# pixelAdapter_f070f6.net
KiCad netlist of a schematic drawn in EAGLE
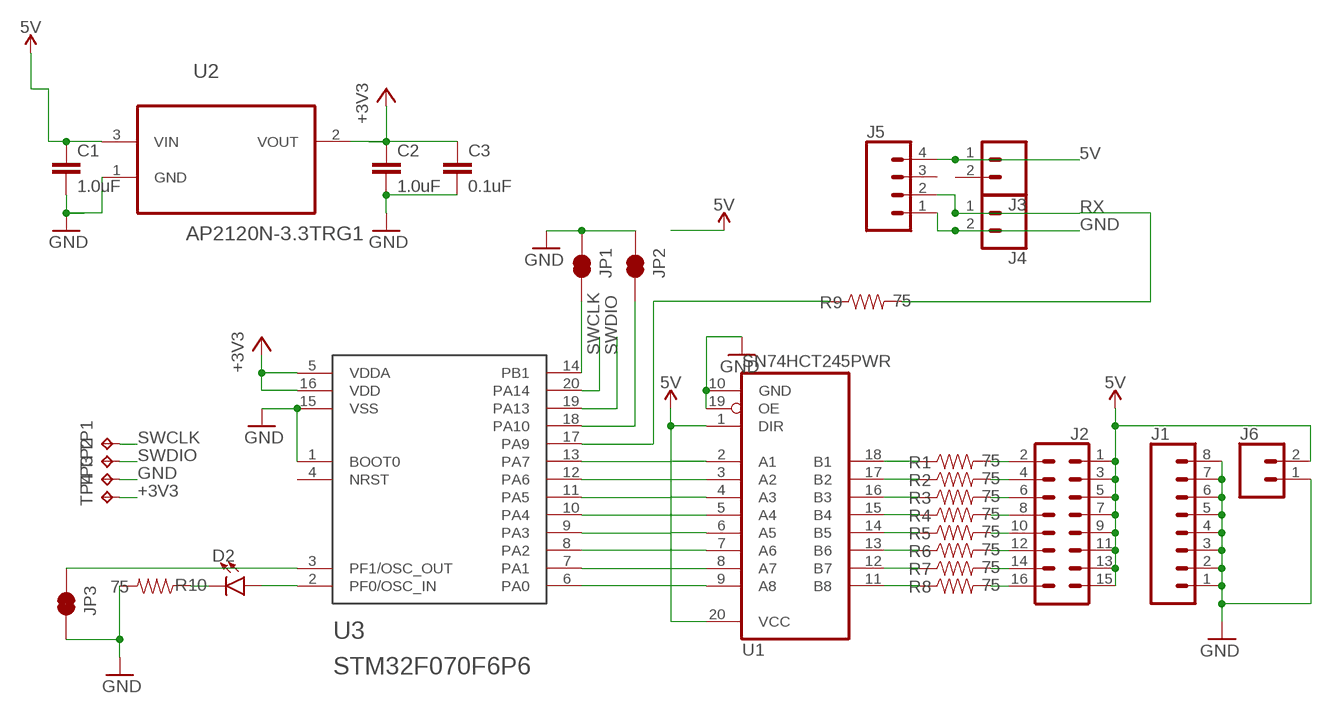
[diagram p0: schematic, sheet 1]

(export (version "E")
  (design (tool "Eeschema 10.0.6"))
  (components
    (comp (ref "C1")
      (value "1.0uF")
      (footprint "eagle-import:0603")
      (libsource (lib "eagle-import") (part "1.0UF-0603-16V-10%"))
    )
    (comp (ref "C2")
      (value "1.0uF")
      (footprint "eagle-import:0603")
      (libsource (lib "eagle-import") (part "1.0UF-0603-16V-10%"))
    )
    (comp (ref "C3")
      (value "0.1uF")
      (footprint "eagle-import:0603")
      (libsource (lib "eagle-import") (part "0.1UF-0603-25V-(+80/-20%)"))
    )
    (comp (ref "D2")
      (value "LED0603")
      (footprint "eagle-import:LED-0603")
      (libsource (lib "eagle-import") (part "LED0603"))
    )
    (comp (ref "J1")
      (value "CONN_08\"")
      (footprint "eagle-import:1X08")
      (libsource (lib "eagle-import") (part "CONN_08{dblquote}"))
    )
    (comp (ref "J2")
      (value "CONN_08X2")
      (footprint "eagle-import:2X8")
      (libsource (lib "eagle-import") (part "CONN_08X2"))
    )
    (comp (ref "J3")
      (value "CONN_025MM")
      (footprint "eagle-import:SCREWTERMINAL-5MM-2")
      (libsource (lib "eagle-import") (part "bens_CONN_025MM"))
    )
    (comp (ref "J4")
      (value "CONN_025MM")
      (footprint "eagle-import:SCREWTERMINAL-5MM-2")
      (libsource (lib "eagle-import") (part "bens_CONN_025MM"))
    )
    (comp (ref "J5")
      (value "CONN_04LOCK")
      (footprint "eagle-import:1X04_LOCK")
      (libsource (lib "eagle-import") (part "CONN_04LOCK"))
    )
    (comp (ref "J6")
      (value "CONN_02")
      (footprint "eagle-import:1X02")
      (libsource (lib "eagle-import") (part "CONN_02"))
    )
    (comp (ref "JP1")
      (value "JUMPER-SMT_2_NC_TRACE_SILK")
      (footprint "eagle-import:SMT-JUMPER_2_NC_TRACE_SILK")
      (libsource (lib "eagle-import") (part "JUMPER-SMT_2_NC_TRACE_SILK"))
    )
    (comp (ref "JP2")
      (value "JUMPER-SMT_2_NC_TRACE_SILK")
      (footprint "eagle-import:SMT-JUMPER_2_NC_TRACE_SILK")
      (libsource (lib "eagle-import") (part "JUMPER-SMT_2_NC_TRACE_SILK"))
    )
    (comp (ref "JP3")
      (value "JUMPER-SMT_2_NC_TRACE_SILK")
      (footprint "eagle-import:SMT-JUMPER_2_NC_TRACE_SILK")
      (libsource (lib "eagle-import") (part "JUMPER-SMT_2_NC_TRACE_SILK"))
    )
    (comp (ref "R1")
      (value "75")
      (footprint "eagle-import:0603")
      (libsource (lib "eagle-import") (part "100OHM-0603-1/4W-5%"))
    )
    (comp (ref "R2")
      (value "75")
      (footprint "eagle-import:0603")
      (libsource (lib "eagle-import") (part "100OHM-0603-1/4W-5%"))
    )
    (comp (ref "R3")
      (value "75")
      (footprint "eagle-import:0603")
      (libsource (lib "eagle-import") (part "100OHM-0603-1/4W-5%"))
    )
    (comp (ref "R4")
      (value "75")
      (footprint "eagle-import:0603")
      (libsource (lib "eagle-import") (part "100OHM-0603-1/4W-5%"))
    )
    (comp (ref "R5")
      (value "75")
      (footprint "eagle-import:0603")
      (libsource (lib "eagle-import") (part "100OHM-0603-1/4W-5%"))
    )
    (comp (ref "R6")
      (value "75")
      (footprint "eagle-import:0603")
      (libsource (lib "eagle-import") (part "100OHM-0603-1/4W-5%"))
    )
    (comp (ref "R7")
      (value "75")
      (footprint "eagle-import:0603")
      (libsource (lib "eagle-import") (part "100OHM-0603-1/4W-5%"))
    )
    (comp (ref "R8")
      (value "75")
      (footprint "eagle-import:0603")
      (libsource (lib "eagle-import") (part "100OHM-0603-1/4W-5%"))
    )
    (comp (ref "R9")
      (value "75")
      (footprint "eagle-import:0603")
      (libsource (lib "eagle-import") (part "100OHM-0603-1/4W-5%"))
    )
    (comp (ref "R10")
      (value "75")
      (footprint "eagle-import:0603")
      (libsource (lib "eagle-import") (part "100OHM-0603-1/4W-5%"))
    )
    (comp (ref "TP1")
      (value "TPTP20SQ")
      (footprint "eagle-import:TP20SQ")
      (libsource (lib "eagle-import") (part "TPTP20SQ"))
    )
    (comp (ref "TP2")
      (value "TPTP20SQ")
      (footprint "eagle-import:TP20SQ")
      (libsource (lib "eagle-import") (part "TPTP20SQ"))
    )
    (comp (ref "TP3")
      (value "TPTP20SQ")
      (footprint "eagle-import:TP20SQ")
      (libsource (lib "eagle-import") (part "TPTP20SQ"))
    )
    (comp (ref "TP4")
      (value "TPTP20SQ")
      (footprint "eagle-import:TP20SQ")
      (libsource (lib "eagle-import") (part "TPTP20SQ"))
    )
    (comp (ref "U1")
      (value "SN74HCT245PWR")
      (footprint "eagle-import:TSSOP20")
      (libsource (lib "eagle-import") (part "74245PW"))
    )
    (comp (ref "U2")
      (value "AP2120N-3.3TRG1")
      (footprint "eagle-import:SOT95P237X112-3N")
      (fields (field (name "MPN") "MCP1700T-3302E/TT"))
      (libsource (lib "eagle-import") (part "MCP1700T-3302E/TT"))
    )
    (comp (ref "U3")
      (value "STM32F070F6P6")
      (footprint "eagle-import:TSSOP-20")
      (libsource (lib "eagle-import") (part "STM32F030XTSSOP20"))
    )
  )
  (nets
    (net (code "1") (name "+3V3") (class "Default")
      (node (ref "C2") (pin "1") (pinfunction "1_1") (pintype "passive"))
      (node (ref "C3") (pin "1") (pinfunction "1_1") (pintype "passive"))
      (node (ref "TP4") (pin "TP") (pinfunction "TP_TP") (pintype "input"))
      (node (ref "U2") (pin "2") (pinfunction "VOUT_2") (pintype "output"))
      (node (ref "U3") (pin "16") (pinfunction "VDD_16") (pintype "bidirectional"))
      (node (ref "U3") (pin "5") (pinfunction "VDDA_5") (pintype "bidirectional"))
    )
    (net (code "2") (name "/RX") (class "Default")
      (node (ref "J4") (pin "1") (pinfunction "1_1") (pintype "passive"))
      (node (ref "J5") (pin "2") (pinfunction "2_2") (pintype "passive"))
      (node (ref "R9") (pin "2") (pinfunction "2_2") (pintype "passive"))
    )
    (net (code "3") (name "/SWCLK") (class "Default")
      (node (ref "TP1") (pin "TP") (pinfunction "TP_TP") (pintype "input"))
      (node (ref "U3") (pin "20") (pinfunction "PA14_20") (pintype "bidirectional"))
    )
    (net (code "4") (name "/SWDIO") (class "Default")
      (node (ref "TP2") (pin "TP") (pinfunction "TP_TP") (pintype "input"))
      (node (ref "U3") (pin "19") (pinfunction "PA13_19") (pintype "bidirectional"))
    )
    (net (code "5") (name "5V") (class "Default")
      (node (ref "C1") (pin "1") (pinfunction "1_1") (pintype "passive"))
      (node (ref "J2") (pin "1") (pinfunction "1_1") (pintype "passive"))
      (node (ref "J2") (pin "11") (pinfunction "11_11") (pintype "passive"))
      (node (ref "J2") (pin "13") (pinfunction "13_13") (pintype "passive"))
      (node (ref "J2") (pin "15") (pinfunction "15_15") (pintype "passive"))
      (node (ref "J2") (pin "3") (pinfunction "3_3") (pintype "passive"))
      (node (ref "J2") (pin "5") (pinfunction "5_5") (pintype "passive"))
      (node (ref "J2") (pin "7") (pinfunction "7_7") (pintype "passive"))
      (node (ref "J2") (pin "9") (pinfunction "9_9") (pintype "passive"))
      (node (ref "J3") (pin "1") (pinfunction "1_1") (pintype "passive"))
      (node (ref "J5") (pin "4") (pinfunction "4_4") (pintype "passive"))
      (node (ref "J6") (pin "2") (pinfunction "2_2") (pintype "passive"))
      (node (ref "U1") (pin "1") (pinfunction "DIR_1") (pintype "input"))
      (node (ref "U1") (pin "20") (pinfunction "VCC_20") (pintype "bidirectional"))
      (node (ref "U2") (pin "3") (pinfunction "VIN_3") (pintype "input"))
    )
    (net (code "6") (name "GND") (class "Default")
      (node (ref "C1") (pin "2") (pinfunction "2_2") (pintype "passive"))
      (node (ref "C2") (pin "2") (pinfunction "2_2") (pintype "passive"))
      (node (ref "C3") (pin "2") (pinfunction "2_2") (pintype "passive"))
      (node (ref "J1") (pin "1") (pinfunction "1_1") (pintype "passive"))
      (node (ref "J1") (pin "2") (pinfunction "2_2") (pintype "passive"))
      (node (ref "J1") (pin "3") (pinfunction "3_3") (pintype "passive"))
      (node (ref "J1") (pin "4") (pinfunction "4_4") (pintype "passive"))
      (node (ref "J1") (pin "5") (pinfunction "5_5") (pintype "passive"))
      (node (ref "J1") (pin "6") (pinfunction "6_6") (pintype "passive"))
      (node (ref "J1") (pin "7") (pinfunction "7_7") (pintype "passive"))
      (node (ref "J1") (pin "8") (pinfunction "8_8") (pintype "passive"))
      (node (ref "J4") (pin "2") (pinfunction "2_2") (pintype "passive"))
      (node (ref "J5") (pin "1") (pinfunction "1_1") (pintype "passive"))
      (node (ref "J6") (pin "1") (pinfunction "1_1") (pintype "passive"))
      (node (ref "JP1") (pin "1") (pinfunction "1_1") (pintype "passive"))
      (node (ref "JP2") (pin "1") (pinfunction "1_1") (pintype "passive"))
      (node (ref "JP3") (pin "2") (pinfunction "2_2") (pintype "passive"))
      (node (ref "R10") (pin "2") (pinfunction "2_2") (pintype "passive"))
      (node (ref "TP3") (pin "TP") (pinfunction "TP_TP") (pintype "input"))
      (node (ref "U1") (pin "10") (pinfunction "GND_10") (pintype "bidirectional"))
      (node (ref "U1") (pin "19") (pinfunction "OE_19") (pintype "input"))
      (node (ref "U2") (pin "1") (pinfunction "GND_1") (pintype "passive"))
      (node (ref "U3") (pin "1") (pinfunction "BOOT0_1") (pintype "bidirectional"))
      (node (ref "U3") (pin "15") (pinfunction "VSS_15") (pintype "bidirectional"))
    )
    (net (code "7") (name "Net-(D2-PadC)") (class "Default")
      (node (ref "D2") (pin "C") (pinfunction "C_C") (pintype "passive"))
      (node (ref "R10") (pin "1") (pinfunction "1_1") (pintype "passive"))
    )
    (net (code "8") (name "Net-(J2-Pad2)") (class "Default")
      (node (ref "J2") (pin "2") (pinfunction "2_2") (pintype "passive"))
      (node (ref "R1") (pin "2") (pinfunction "2_2") (pintype "passive"))
    )
    (net (code "9") (name "Net-(J2-Pad4)") (class "Default")
      (node (ref "J2") (pin "4") (pinfunction "4_4") (pintype "passive"))
      (node (ref "R2") (pin "2") (pinfunction "2_2") (pintype "passive"))
    )
    (net (code "10") (name "Net-(J2-Pad6)") (class "Default")
      (node (ref "J2") (pin "6") (pinfunction "6_6") (pintype "passive"))
      (node (ref "R3") (pin "2") (pinfunction "2_2") (pintype "passive"))
    )
    (net (code "11") (name "Net-(J2-Pad8)") (class "Default")
      (node (ref "J2") (pin "8") (pinfunction "8_8") (pintype "passive"))
      (node (ref "R4") (pin "2") (pinfunction "2_2") (pintype "passive"))
    )
    (net (code "12") (name "Net-(J2-Pad10)") (class "Default")
      (node (ref "J2") (pin "10") (pinfunction "10_10") (pintype "passive"))
      (node (ref "R5") (pin "2") (pinfunction "2_2") (pintype "passive"))
    )
    (net (code "13") (name "Net-(J2-Pad12)") (class "Default")
      (node (ref "J2") (pin "12") (pinfunction "12_12") (pintype "passive"))
      (node (ref "R6") (pin "2") (pinfunction "2_2") (pintype "passive"))
    )
    (net (code "14") (name "Net-(J2-Pad14)") (class "Default")
      (node (ref "J2") (pin "14") (pinfunction "14_14") (pintype "passive"))
      (node (ref "R7") (pin "2") (pinfunction "2_2") (pintype "passive"))
    )
    (net (code "15") (name "Net-(J2-Pad16)") (class "Default")
      (node (ref "J2") (pin "16") (pinfunction "16_16") (pintype "passive"))
      (node (ref "R8") (pin "2") (pinfunction "2_2") (pintype "passive"))
    )
    (net (code "16") (name "Net-(U1-A1)") (class "Default")
      (node (ref "U1") (pin "2") (pinfunction "A1_2") (pintype "bidirectional"))
      (node (ref "U3") (pin "13") (pinfunction "PA7_13") (pintype "bidirectional"))
    )
    (net (code "17") (name "Net-(U1-A2)") (class "Default")
      (node (ref "U1") (pin "3") (pinfunction "A2_3") (pintype "bidirectional"))
      (node (ref "U3") (pin "12") (pinfunction "PA6_12") (pintype "bidirectional"))
    )
    (net (code "18") (name "Net-(U1-A3)") (class "Default")
      (node (ref "U1") (pin "4") (pinfunction "A3_4") (pintype "bidirectional"))
      (node (ref "U3") (pin "11") (pinfunction "PA5_11") (pintype "bidirectional"))
    )
    (net (code "19") (name "Net-(U1-A4)") (class "Default")
      (node (ref "U1") (pin "5") (pinfunction "A4_5") (pintype "bidirectional"))
      (node (ref "U3") (pin "10") (pinfunction "PA4_10") (pintype "bidirectional"))
    )
    (net (code "20") (name "Net-(U1-A5)") (class "Default")
      (node (ref "U1") (pin "6") (pinfunction "A5_6") (pintype "bidirectional"))
      (node (ref "U3") (pin "9") (pinfunction "PA3_9") (pintype "bidirectional"))
    )
    (net (code "21") (name "Net-(U1-A6)") (class "Default")
      (node (ref "U1") (pin "7") (pinfunction "A6_7") (pintype "bidirectional"))
      (node (ref "U3") (pin "8") (pinfunction "PA2_8") (pintype "bidirectional"))
    )
    (net (code "22") (name "Net-(U1-A7)") (class "Default")
      (node (ref "U1") (pin "8") (pinfunction "A7_8") (pintype "bidirectional"))
      (node (ref "U3") (pin "7") (pinfunction "PA1_7") (pintype "bidirectional"))
    )
    (net (code "23") (name "Net-(U1-A8)") (class "Default")
      (node (ref "U1") (pin "9") (pinfunction "A8_9") (pintype "bidirectional"))
      (node (ref "U3") (pin "6") (pinfunction "PA0_6") (pintype "bidirectional"))
    )
    (net (code "24") (name "Net-(U1-B1)") (class "Default")
      (node (ref "R1") (pin "1") (pinfunction "1_1") (pintype "passive"))
      (node (ref "U1") (pin "18") (pinfunction "B1_18") (pintype "bidirectional"))
    )
    (net (code "25") (name "Net-(U1-B2)") (class "Default")
      (node (ref "R2") (pin "1") (pinfunction "1_1") (pintype "passive"))
      (node (ref "U1") (pin "17") (pinfunction "B2_17") (pintype "bidirectional"))
    )
    (net (code "26") (name "Net-(U1-B3)") (class "Default")
      (node (ref "R3") (pin "1") (pinfunction "1_1") (pintype "passive"))
      (node (ref "U1") (pin "16") (pinfunction "B3_16") (pintype "bidirectional"))
    )
    (net (code "27") (name "Net-(U1-B4)") (class "Default")
      (node (ref "R4") (pin "1") (pinfunction "1_1") (pintype "passive"))
      (node (ref "U1") (pin "15") (pinfunction "B4_15") (pintype "bidirectional"))
    )
    (net (code "28") (name "Net-(U1-B5)") (class "Default")
      (node (ref "R5") (pin "1") (pinfunction "1_1") (pintype "passive"))
      (node (ref "U1") (pin "14") (pinfunction "B5_14") (pintype "bidirectional"))
    )
    (net (code "29") (name "Net-(U1-B6)") (class "Default")
      (node (ref "R6") (pin "1") (pinfunction "1_1") (pintype "passive"))
      (node (ref "U1") (pin "13") (pinfunction "B6_13") (pintype "bidirectional"))
    )
    (net (code "30") (name "Net-(U1-B7)") (class "Default")
      (node (ref "R7") (pin "1") (pinfunction "1_1") (pintype "passive"))
      (node (ref "U1") (pin "12") (pinfunction "B7_12") (pintype "bidirectional"))
    )
    (net (code "31") (name "Net-(U1-B8)") (class "Default")
      (node (ref "R8") (pin "1") (pinfunction "1_1") (pintype "passive"))
      (node (ref "U1") (pin "11") (pinfunction "B8_11") (pintype "bidirectional"))
    )
    (net (code "32") (name "Net-(U3-PA9)") (class "Default")
      (node (ref "R9") (pin "1") (pinfunction "1_1") (pintype "passive"))
      (node (ref "U3") (pin "17") (pinfunction "PA9_17") (pintype "bidirectional"))
    )
    (net (code "33") (name "Net-(U3-PA10)") (class "Default")
      (node (ref "JP2") (pin "2") (pinfunction "2_2") (pintype "passive"))
      (node (ref "U3") (pin "18") (pinfunction "PA10_18") (pintype "bidirectional"))
    )
    (net (code "34") (name "Net-(U3-PB1)") (class "Default")
      (node (ref "JP1") (pin "2") (pinfunction "2_2") (pintype "passive"))
      (node (ref "U3") (pin "14") (pinfunction "PB1_14") (pintype "bidirectional"))
    )
    (net (code "35") (name "Net-(U3-PF0{slash}OSC_IN)") (class "Default")
      (node (ref "D2") (pin "A") (pinfunction "A_A") (pintype "passive"))
      (node (ref "U3") (pin "2") (pinfunction "PF0/OSC_IN_2") (pintype "bidirectional"))
    )
    (net (code "36") (name "Net-(U3-PF1{slash}OSC_OUT)") (class "Default")
      (node (ref "JP3") (pin "1") (pinfunction "1_1") (pintype "passive"))
      (node (ref "U3") (pin "3") (pinfunction "PF1/OSC_OUT_3") (pintype "bidirectional"))
    )
    (net (code "37") (name "unconnected-(J3-Pad2)") (class "Default")
      (node (ref "J3") (pin "2") (pinfunction "2_2") (pintype "passive"))
    )
    (net (code "38") (name "unconnected-(J5-Pad3)") (class "Default")
      (node (ref "J5") (pin "3") (pinfunction "3_3") (pintype "passive"))
    )
    (net (code "39") (name "unconnected-(U3-NRST-Pad4)") (class "Default")
      (node (ref "U3") (pin "4") (pinfunction "NRST_4") (pintype "bidirectional"))
    )
  )
)
